# Power.net
KiCad netlist of a schematic drawn in Altium Designer
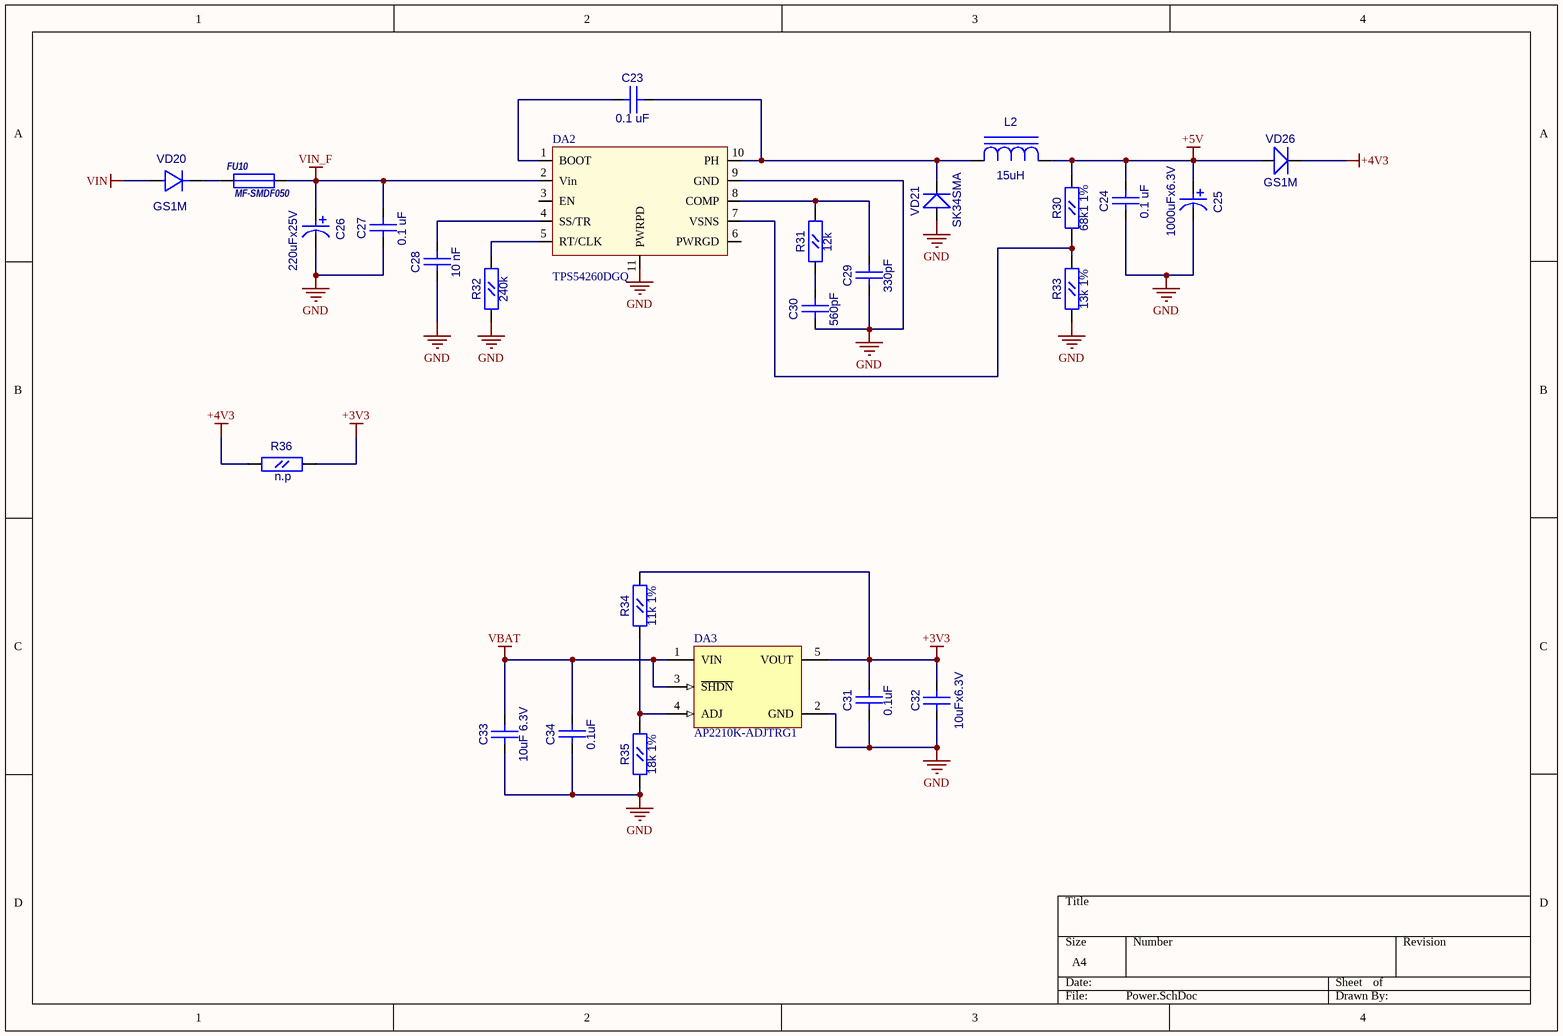
[diagram p0: Power.SchDoc]

(export (version "E")
  (design (tool "Eeschema 10.0.6"))
  (components
    (comp (ref "C23")
      (value "0.1 uF")
      (footprint "CC0603")
      (description "CC0603")
      (libsource (lib "gprs_modem_2") (part "CC0603"))
    )
    (comp (ref "C24")
      (value "0.1 uF")
      (footprint "CC0603")
      (description "CC0603")
      (libsource (lib "gprs_modem_2") (part "CC0603"))
    )
    (comp (ref "C25")
      (value "1000uFx6.3V")
      (footprint "CC8X3.5")
      (description "CAP0.35")
      (libsource (lib "gprs_modem_2") (part "CAP0.35"))
    )
    (comp (ref "C26")
      (value "220uFx25V")
      (footprint "CC8X3.5")
      (description "CAP0.35")
      (libsource (lib "fizik_lib") (part "CAP0.35"))
    )
    (comp (ref "C27")
      (value "0.1 uF")
      (footprint "CC0603")
      (description "CC0603")
      (libsource (lib "gprs_modem_2") (part "CC0603"))
    )
    (comp (ref "C28")
      (value "10 nF")
      (footprint "CC0603")
      (description "CC0603")
      (libsource (lib "gprs_modem_2") (part "CC0603"))
    )
    (comp (ref "C29")
      (value "330pF")
      (footprint "CC0603")
      (description "CC0603")
      (libsource (lib "gprs_modem_2") (part "CC0603"))
    )
    (comp (ref "C30")
      (value "560pF")
      (footprint "CC0603")
      (description "CC0603")
      (libsource (lib "gprs_modem_2") (part "CC0603"))
    )
    (comp (ref "C31")
      (value "0.1uF")
      (footprint "CC0603")
      (description "CC0603")
      (libsource (lib "gprs_modem_2") (part "CC0603"))
    )
    (comp (ref "C32")
      (value "10uFx6.3V")
      (footprint "CC0805")
      (description "CC0805")
      (libsource (lib "gprs_modem_2") (part "CC0805"))
    )
    (comp (ref "C33")
      (value "10uF 6.3V")
      (footprint "CC0805")
      (description "CC0805")
      (libsource (lib "gprs_modem_2") (part "CC0805"))
    )
    (comp (ref "C34")
      (value "0.1uF")
      (footprint "CC0603")
      (description "CC0603")
      (libsource (lib "gprs_modem_2") (part "CC0603"))
    )
    (comp (ref "DA2")
      (value "TPS54260DGQ")
      (footprint "S-PDSO-G10")
      (libsource (lib "gprs_modem_2") (part "TPS54260DGQ"))
    )
    (comp (ref "DA3")
      (value "AP2210K-ADJTRG1")
      (footprint "SOT23-5")
      (fields (field (name "PUBLISHER") "Altium Limited"))
      (libsource (lib "gprs_modem_2") (part "MCP1824T-ADJE/OT"))
    )
    (comp (ref "FU10")
      (value "MF-SMDF050")
      (footprint "MF-SMDF")
      (description "MF-SMDF")
      (libsource (lib "fizik_lib") (part "MF-SMDF"))
    )
    (comp (ref "L2")
      (value "15uH")
      (footprint "SDR0805")
      (description "SDR0805")
      (libsource (lib "gprs_modem_2") (part "SDR0805"))
    )
    (comp (ref "R30")
      (value "68k1 1%")
      (footprint "RC0603")
      (description "RC0603")
      (libsource (lib "gprs_modem_2") (part "RC0603"))
    )
    (comp (ref "R31")
      (value "12k")
      (footprint "RC0603")
      (description "RC0603")
      (libsource (lib "gprs_modem_2") (part "RC0603"))
    )
    (comp (ref "R32")
      (value "240k")
      (footprint "RC0603")
      (description "RC0603")
      (libsource (lib "gprs_modem_2") (part "RC0603"))
    )
    (comp (ref "R33")
      (value "13k 1%")
      (footprint "RC0603")
      (description "RC0603")
      (libsource (lib "gprs_modem_2") (part "RC0603"))
    )
    (comp (ref "R34")
      (value "11k 1%")
      (footprint "RC0603")
      (description "RC0603")
      (libsource (lib "gprs_modem_2") (part "RC0603"))
    )
    (comp (ref "R35")
      (value "18k 1%")
      (footprint "RC0603")
      (description "RC0603")
      (libsource (lib "gprs_modem_2") (part "RC0603"))
    )
    (comp (ref "R36")
      (value "n.p")
      (footprint "RC0805")
      (description "RC0805")
      (libsource (lib "gprs_modem_2") (part "RC0805"))
    )
    (comp (ref "VD20") (value "GS1M") (footprint "SMA") (libsource (lib "gprs_modem_2") (part "GS1M")))
    (comp (ref "VD21")
      (value "SK34SMA")
      (footprint "SMA")
      (description "Schottky Rectifier")
      (libsource (lib "gprs_modem") (part "SK34SMA"))
    )
    (comp (ref "VD26")
      (value "GS1M")
      (footprint "SMA")
      (description "Schottky Rectifier")
      (libsource (lib "gprs_modem_2") (part "SS14"))
    )
  )
  (nets
    (net (code "1") (name "+3V3") (class "Default")
      (node (ref "C31") (pin "1") (pinfunction "A_1") (pintype "passive"))
      (node (ref "C32") (pin "2") (pinfunction "B_2") (pintype "passive"))
      (node (ref "DA3") (pin "5") (pinfunction "VOUT_5") (pintype "power_in"))
      (node (ref "R34") (pin "2") (pinfunction "B_2") (pintype "passive"))
      (node (ref "R36") (pin "2") (pinfunction "B_2") (pintype "passive"))
    )
    (net (code "2") (name "+4V3") (class "Default")
      (node (ref "R36") (pin "1") (pinfunction "A_1") (pintype "passive"))
      (node (ref "VD26") (pin "2") (pinfunction "K_2") (pintype "passive"))
    )
    (net (code "3") (name "+5V") (class "Default")
      (node (ref "C24") (pin "1") (pinfunction "A_1") (pintype "passive"))
      (node (ref "C25") (pin "1") (pintype "passive"))
      (node (ref "L2") (pin "2") (pinfunction "A_2") (pintype "passive"))
      (node (ref "R30") (pin "2") (pinfunction "B_2") (pintype "passive"))
      (node (ref "VD26") (pin "1") (pinfunction "A_1") (pintype "passive"))
    )
    (net (code "4") (name "GND") (class "Default")
      (node (ref "C24") (pin "2") (pinfunction "B_2") (pintype "passive"))
      (node (ref "C25") (pin "2") (pintype "passive"))
      (node (ref "C26") (pin "2") (pintype "passive"))
      (node (ref "C27") (pin "2") (pinfunction "B_2") (pintype "passive"))
      (node (ref "C28") (pin "2") (pinfunction "B_2") (pintype "passive"))
      (node (ref "C29") (pin "2") (pinfunction "B_2") (pintype "passive"))
      (node (ref "C30") (pin "2") (pinfunction "B_2") (pintype "passive"))
      (node (ref "C31") (pin "2") (pinfunction "B_2") (pintype "passive"))
      (node (ref "C32") (pin "1") (pinfunction "A_1") (pintype "passive"))
      (node (ref "C33") (pin "1") (pinfunction "A_1") (pintype "passive"))
      (node (ref "C34") (pin "2") (pinfunction "B_2") (pintype "passive"))
      (node (ref "DA2") (pin "11") (pinfunction "PWRPD_11") (pintype "passive"))
      (node (ref "DA2") (pin "9") (pinfunction "GND_9") (pintype "passive"))
      (node (ref "DA3") (pin "2") (pinfunction "GND_2") (pintype "power_in"))
      (node (ref "R32") (pin "1") (pinfunction "A_1") (pintype "passive"))
      (node (ref "R33") (pin "1") (pinfunction "A_1") (pintype "passive"))
      (node (ref "R35") (pin "1") (pinfunction "A_1") (pintype "passive"))
      (node (ref "VD21") (pin "1") (pinfunction "A_1") (pintype "passive"))
    )
    (net (code "5") (name "Net-(C23-A)") (class "Default")
      (node (ref "C23") (pin "1") (pinfunction "A_1") (pintype "passive"))
      (node (ref "DA2") (pin "10") (pinfunction "PH_10") (pintype "passive"))
      (node (ref "L2") (pin "1") (pinfunction "C_1") (pintype "passive"))
      (node (ref "VD21") (pin "2") (pinfunction "K_2") (pintype "passive"))
    )
    (net (code "6") (name "Net-(C23-B)") (class "Default")
      (node (ref "C23") (pin "2") (pinfunction "B_2") (pintype "passive"))
      (node (ref "DA2") (pin "1") (pinfunction "BOOT_1") (pintype "passive"))
    )
    (net (code "7") (name "Net-(C28-A)") (class "Default")
      (node (ref "C28") (pin "1") (pinfunction "A_1") (pintype "passive"))
      (node (ref "DA2") (pin "4") (pinfunction "SS/TR_4") (pintype "passive"))
    )
    (net (code "8") (name "Net-(C29-A)") (class "Default")
      (node (ref "C29") (pin "1") (pinfunction "A_1") (pintype "passive"))
      (node (ref "DA2") (pin "8") (pinfunction "COMP_8") (pintype "passive"))
      (node (ref "R31") (pin "2") (pinfunction "B_2") (pintype "passive"))
    )
    (net (code "9") (name "Net-(C30-A)") (class "Default")
      (node (ref "C30") (pin "1") (pinfunction "A_1") (pintype "passive"))
      (node (ref "R31") (pin "1") (pinfunction "A_1") (pintype "passive"))
    )
    (net (code "10") (name "Net-(DA2-RT{slash}CLK)") (class "Default")
      (node (ref "DA2") (pin "5") (pinfunction "RT/CLK_5") (pintype "passive"))
      (node (ref "R32") (pin "2") (pinfunction "B_2") (pintype "passive"))
    )
    (net (code "11") (name "Net-(DA2-VSNS)") (class "Default")
      (node (ref "DA2") (pin "7") (pinfunction "VSNS_7") (pintype "passive"))
      (node (ref "R30") (pin "1") (pinfunction "A_1") (pintype "passive"))
      (node (ref "R33") (pin "2") (pinfunction "B_2") (pintype "passive"))
    )
    (net (code "12") (name "Net-(DA3-ADJ)") (class "Default")
      (node (ref "DA3") (pin "4") (pinfunction "ADJ_4") (pintype "input"))
      (node (ref "R34") (pin "1") (pinfunction "A_1") (pintype "passive"))
      (node (ref "R35") (pin "2") (pinfunction "B_2") (pintype "passive"))
    )
    (net (code "13") (name "Net-(VD20-K)") (class "Default")
      (node (ref "FU10") (pin "1") (pintype "passive"))
      (node (ref "VD20") (pin "2") (pinfunction "K_2") (pintype "passive"))
    )
    (net (code "14") (name "VBAT") (class "Default")
      (node (ref "C33") (pin "2") (pinfunction "B_2") (pintype "passive"))
      (node (ref "C34") (pin "1") (pinfunction "A_1") (pintype "passive"))
      (node (ref "DA3") (pin "1") (pinfunction "VIN_1") (pintype "power_in"))
      (node (ref "DA3") (pin "3") (pinfunction "~{SHDN}_3") (pintype "input"))
    )
    (net (code "15") (name "VIN") (class "Default")
      (node (ref "VD20") (pin "1") (pinfunction "A_1") (pintype "passive"))
    )
    (net (code "16") (name "VIN_F") (class "Default")
      (node (ref "C26") (pin "1") (pintype "passive"))
      (node (ref "C27") (pin "1") (pinfunction "A_1") (pintype "passive"))
      (node (ref "DA2") (pin "2") (pinfunction "Vin_2") (pintype "passive"))
      (node (ref "FU10") (pin "2") (pintype "passive"))
    )
    (net (code "17") (name "unconnected-(DA2-EN-Pad3)") (class "Default")
      (node (ref "DA2") (pin "3") (pinfunction "EN_3") (pintype "passive"))
    )
    (net (code "18") (name "unconnected-(DA2-PWRGD-Pad6)") (class "Default")
      (node (ref "DA2") (pin "6") (pinfunction "PWRGD_6") (pintype "passive"))
    )
  )
)
